# untitled.net
KiCad netlist of a schematic drawn in EAGLE
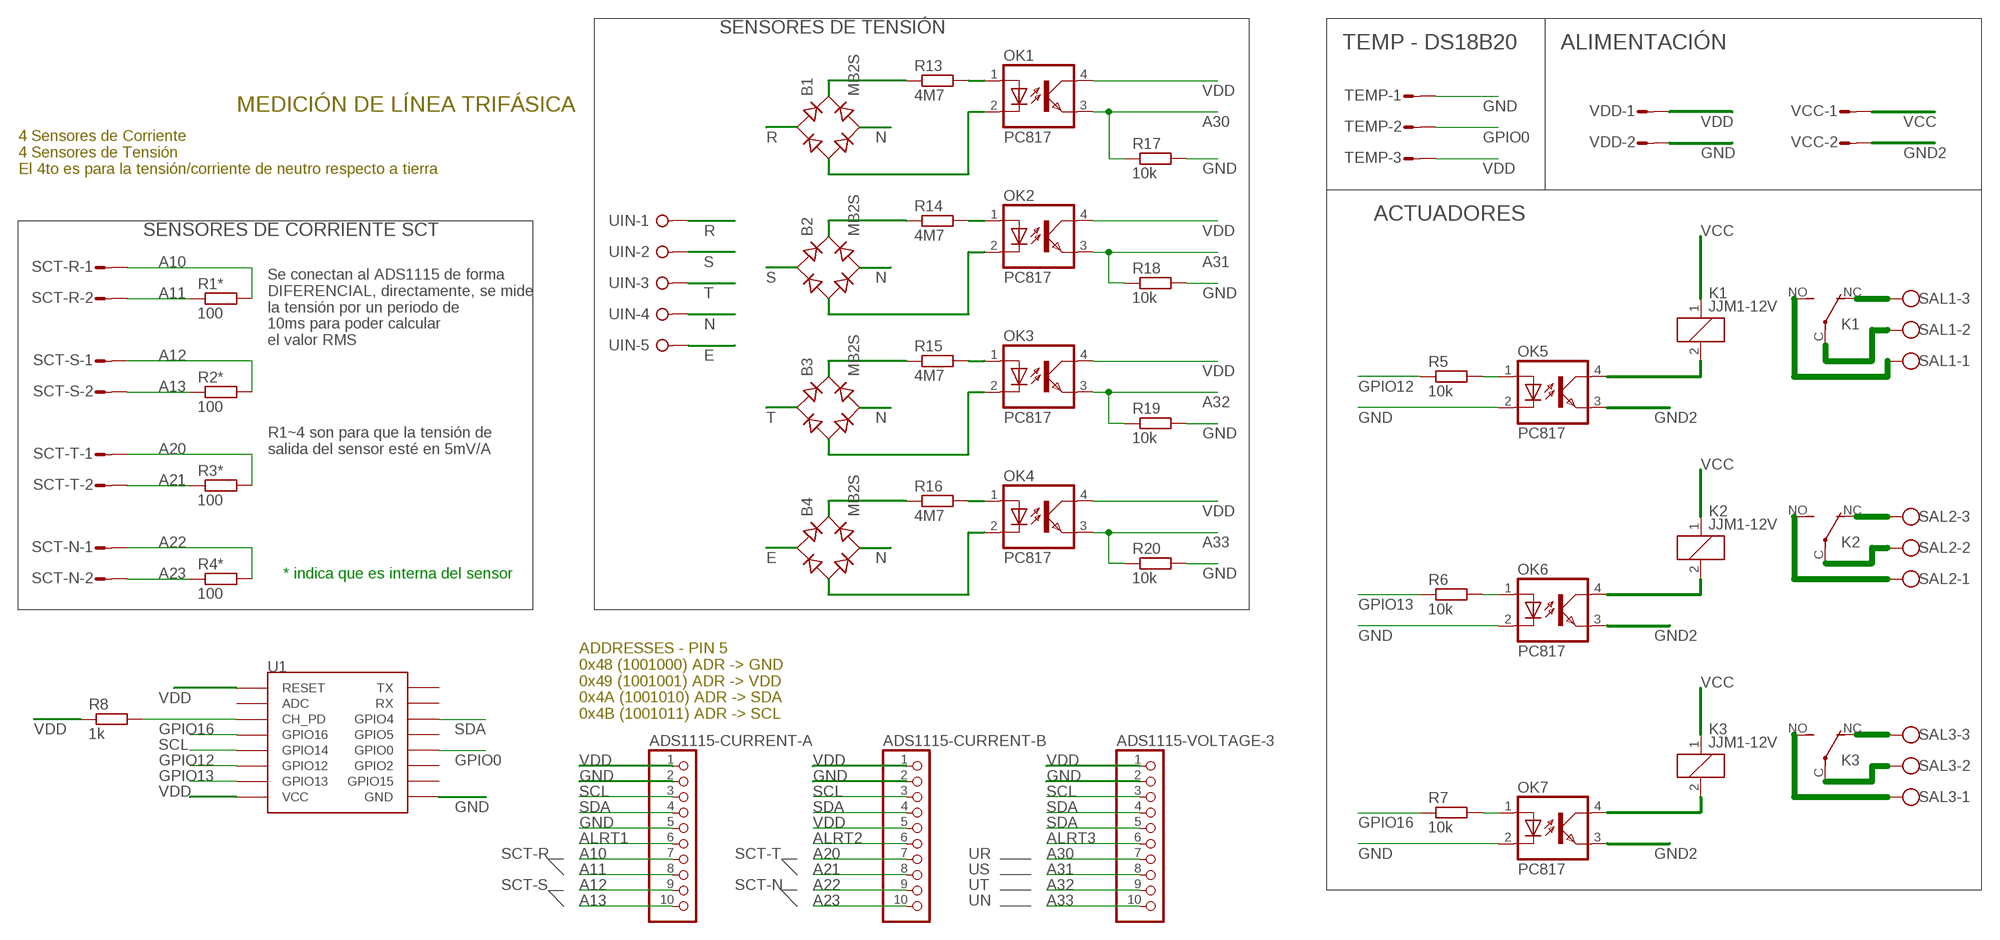
[diagram p0: schematic, sheet 1]

(export (version "E")
  (design (tool "Eeschema 10.0.6"))
  (components
    (comp (ref "ADS1115-CURRENT-A")
      (value "PINHD-1X10")
      (footprint "eagle-import:1X10")
      (libsource (lib "eagle-import") (part "PINHD-1X10"))
    )
    (comp (ref "ADS1115-CURRENT-B")
      (value "PINHD-1X10")
      (footprint "eagle-import:1X10")
      (libsource (lib "eagle-import") (part "PINHD-1X10"))
    )
    (comp (ref "ADS1115-VOLTAGE-3")
      (value "PINHD-1X10")
      (footprint "eagle-import:1X10")
      (libsource (lib "eagle-import") (part "PINHD-1X10"))
    )
    (comp (ref "B1")
      (value "MB2S")
      (footprint "eagle-import:SOIC-4")
      (libsource (lib "eagle-import") (part "MBS2"))
    )
    (comp (ref "B2")
      (value "MB2S")
      (footprint "eagle-import:SOIC-4")
      (libsource (lib "eagle-import") (part "MBS2"))
    )
    (comp (ref "B3")
      (value "MB2S")
      (footprint "eagle-import:SOIC-4")
      (libsource (lib "eagle-import") (part "MBS2"))
    )
    (comp (ref "B4")
      (value "MB2S")
      (footprint "eagle-import:SOIC-4")
      (libsource (lib "eagle-import") (part "MBS2"))
    )
    (comp (ref "K1")
      (value "JJM1-12V")
      (footprint "eagle-import:JJM1C")
      (fields (field (name "MF") "AROMAT/ MATSUSHITA"))
      (libsource (lib "eagle-import") (part "JJM1-12V"))
    )
    (comp (ref "K2")
      (value "JJM1-12V")
      (footprint "eagle-import:JJM1C")
      (fields (field (name "MF") "AROMAT/ MATSUSHITA"))
      (libsource (lib "eagle-import") (part "JJM1-12V"))
    )
    (comp (ref "K3")
      (value "JJM1-12V")
      (footprint "eagle-import:JJM1C")
      (fields (field (name "MF") "AROMAT/ MATSUSHITA"))
      (libsource (lib "eagle-import") (part "JJM1-12V"))
    )
    (comp (ref "OK1")
      (value "PC817")
      (footprint "eagle-import:DIL04")
      (fields (field (name "MPN") "PC817X4J000F"))
      (libsource (lib "eagle-import") (part "PC817"))
    )
    (comp (ref "OK2")
      (value "PC817")
      (footprint "eagle-import:DIL04")
      (fields (field (name "MPN") "PC817X4J000F"))
      (libsource (lib "eagle-import") (part "PC817"))
    )
    (comp (ref "OK3")
      (value "PC817")
      (footprint "eagle-import:DIL04")
      (fields (field (name "MPN") "PC817X4J000F"))
      (libsource (lib "eagle-import") (part "PC817"))
    )
    (comp (ref "OK4")
      (value "PC817")
      (footprint "eagle-import:DIL04")
      (fields (field (name "MPN") "PC817X4J000F"))
      (libsource (lib "eagle-import") (part "PC817"))
    )
    (comp (ref "OK5")
      (value "PC817")
      (footprint "eagle-import:DIL04")
      (fields (field (name "MPN") "PC817X4J000F"))
      (libsource (lib "eagle-import") (part "PC817"))
    )
    (comp (ref "OK6")
      (value "PC817")
      (footprint "eagle-import:DIL04")
      (fields (field (name "MPN") "PC817X4J000F"))
      (libsource (lib "eagle-import") (part "PC817"))
    )
    (comp (ref "OK7")
      (value "PC817")
      (footprint "eagle-import:DIL04")
      (fields (field (name "MPN") "PC817X4J000F"))
      (libsource (lib "eagle-import") (part "PC817"))
    )
    (comp (ref "R1*")
      (value "100")
      (footprint "eagle-import:M0805")
      (libsource (lib "eagle-import") (part "R-EU_M0805"))
    )
    (comp (ref "R2*")
      (value "100")
      (footprint "eagle-import:M0805")
      (libsource (lib "eagle-import") (part "R-EU_M0805"))
    )
    (comp (ref "R3*")
      (value "100")
      (footprint "eagle-import:M0805")
      (libsource (lib "eagle-import") (part "R-EU_M0805"))
    )
    (comp (ref "R4*")
      (value "100")
      (footprint "eagle-import:M0805")
      (libsource (lib "eagle-import") (part "R-EU_M0805"))
    )
    (comp (ref "R5")
      (value "10k")
      (footprint "eagle-import:M0805")
      (libsource (lib "eagle-import") (part "R-EU_M0805"))
    )
    (comp (ref "R6")
      (value "10k")
      (footprint "eagle-import:M0805")
      (libsource (lib "eagle-import") (part "R-EU_M0805"))
    )
    (comp (ref "R7")
      (value "10k")
      (footprint "eagle-import:M0805")
      (libsource (lib "eagle-import") (part "R-EU_M0805"))
    )
    (comp (ref "R8")
      (value "1k")
      (footprint "eagle-import:M0805")
      (libsource (lib "eagle-import") (part "R-EU_M0805"))
    )
    (comp (ref "R13")
      (value "4M7")
      (footprint "eagle-import:M0805")
      (libsource (lib "eagle-import") (part "R-EU_M0805"))
    )
    (comp (ref "R14")
      (value "4M7")
      (footprint "eagle-import:M0805")
      (libsource (lib "eagle-import") (part "R-EU_M0805"))
    )
    (comp (ref "R15")
      (value "4M7")
      (footprint "eagle-import:M0805")
      (libsource (lib "eagle-import") (part "R-EU_M0805"))
    )
    (comp (ref "R16")
      (value "4M7")
      (footprint "eagle-import:M0805")
      (libsource (lib "eagle-import") (part "R-EU_M0805"))
    )
    (comp (ref "R17")
      (value "10k")
      (footprint "eagle-import:M0805")
      (libsource (lib "eagle-import") (part "R-EU_M0805"))
    )
    (comp (ref "R18")
      (value "10k")
      (footprint "eagle-import:M0805")
      (libsource (lib "eagle-import") (part "R-EU_M0805"))
    )
    (comp (ref "R19")
      (value "10k")
      (footprint "eagle-import:M0805")
      (libsource (lib "eagle-import") (part "R-EU_M0805"))
    )
    (comp (ref "R20")
      (value "10k")
      (footprint "eagle-import:M0805")
      (libsource (lib "eagle-import") (part "R-EU_M0805"))
    )
    (comp (ref "SAL1")
      (value "W237-103")
      (footprint "eagle-import:W237-103")
      (fields (field (name "MPN") "237-103"))
      (libsource (lib "eagle-import") (part "W237-103"))
    )
    (comp (ref "SAL2")
      (value "W237-103")
      (footprint "eagle-import:W237-103")
      (fields (field (name "MPN") "237-103"))
      (libsource (lib "eagle-import") (part "W237-103"))
    )
    (comp (ref "SAL3")
      (value "W237-103")
      (footprint "eagle-import:W237-103")
      (fields (field (name "MPN") "237-103"))
      (libsource (lib "eagle-import") (part "W237-103"))
    )
    (comp (ref "SCT-N")
      (value "S02P")
      (footprint "eagle-import:S02P")
      (libsource (lib "eagle-import") (part "S02P"))
    )
    (comp (ref "SCT-R")
      (value "S02P")
      (footprint "eagle-import:S02P")
      (libsource (lib "eagle-import") (part "S02P"))
    )
    (comp (ref "SCT-S")
      (value "S02P")
      (footprint "eagle-import:S02P")
      (libsource (lib "eagle-import") (part "S02P"))
    )
    (comp (ref "SCT-T")
      (value "S02P")
      (footprint "eagle-import:S02P")
      (libsource (lib "eagle-import") (part "S02P"))
    )
    (comp (ref "TEMP")
      (value "S03P")
      (footprint "eagle-import:S03P")
      (libsource (lib "eagle-import") (part "S03P"))
    )
    (comp (ref "U1")
      (value "ESP12SMD")
      (footprint "eagle-import:ESP12-SMD")
      (libsource (lib "eagle-import") (part "ESP12SMD"))
    )
    (comp (ref "UIN")
      (value "W237-05P")
      (footprint "eagle-import:W237-5P")
      (libsource (lib "eagle-import") (part "W237-05P"))
    )
    (comp (ref "VCC")
      (value "S02P")
      (footprint "eagle-import:S02P")
      (libsource (lib "eagle-import") (part "S02P"))
    )
    (comp (ref "VDD")
      (value "S02P")
      (footprint "eagle-import:S02P")
      (libsource (lib "eagle-import") (part "S02P"))
    )
  )
  (nets
    (net (code "1") (name "/A10") (class "Default")
      (node (ref "ADS1115-CURRENT-A") (pin "7") (pinfunction "7_7") (pintype "passive"))
      (node (ref "R1*") (pin "2") (pinfunction "2_2") (pintype "passive"))
      (node (ref "SCT-R") (pin "1") (pinfunction "S_1") (pintype "passive"))
    )
    (net (code "2") (name "/A11") (class "Default")
      (node (ref "ADS1115-CURRENT-A") (pin "8") (pinfunction "8_8") (pintype "passive"))
      (node (ref "R1*") (pin "1") (pinfunction "1_1") (pintype "passive"))
      (node (ref "SCT-R") (pin "2") (pinfunction "S_2") (pintype "passive"))
    )
    (net (code "3") (name "/A12") (class "Default")
      (node (ref "ADS1115-CURRENT-A") (pin "9") (pinfunction "9_9") (pintype "passive"))
      (node (ref "R2*") (pin "2") (pinfunction "2_2") (pintype "passive"))
      (node (ref "SCT-S") (pin "1") (pinfunction "S_1") (pintype "passive"))
    )
    (net (code "4") (name "/A13") (class "Default")
      (node (ref "ADS1115-CURRENT-A") (pin "10") (pinfunction "10_10") (pintype "passive"))
      (node (ref "R2*") (pin "1") (pinfunction "1_1") (pintype "passive"))
      (node (ref "SCT-S") (pin "2") (pinfunction "S_2") (pintype "passive"))
    )
    (net (code "5") (name "/A20") (class "Default")
      (node (ref "ADS1115-CURRENT-B") (pin "7") (pinfunction "7_7") (pintype "passive"))
      (node (ref "R3*") (pin "2") (pinfunction "2_2") (pintype "passive"))
      (node (ref "SCT-T") (pin "1") (pinfunction "S_1") (pintype "passive"))
    )
    (net (code "6") (name "/A21") (class "Default")
      (node (ref "ADS1115-CURRENT-B") (pin "8") (pinfunction "8_8") (pintype "passive"))
      (node (ref "R3*") (pin "1") (pinfunction "1_1") (pintype "passive"))
      (node (ref "SCT-T") (pin "2") (pinfunction "S_2") (pintype "passive"))
    )
    (net (code "7") (name "/A22") (class "Default")
      (node (ref "ADS1115-CURRENT-B") (pin "9") (pinfunction "9_9") (pintype "passive"))
      (node (ref "R4*") (pin "2") (pinfunction "2_2") (pintype "passive"))
      (node (ref "SCT-N") (pin "1") (pinfunction "S_1") (pintype "passive"))
    )
    (net (code "8") (name "/A23") (class "Default")
      (node (ref "ADS1115-CURRENT-B") (pin "10") (pinfunction "10_10") (pintype "passive"))
      (node (ref "R4*") (pin "1") (pinfunction "1_1") (pintype "passive"))
      (node (ref "SCT-N") (pin "2") (pinfunction "S_2") (pintype "passive"))
    )
    (net (code "9") (name "/A30") (class "Default")
      (node (ref "ADS1115-VOLTAGE-3") (pin "7") (pinfunction "7_7") (pintype "passive"))
      (node (ref "OK1") (pin "3") (pinfunction "EMIT_3") (pintype "passive"))
      (node (ref "R17") (pin "1") (pinfunction "1_1") (pintype "passive"))
    )
    (net (code "10") (name "/A31") (class "Default")
      (node (ref "ADS1115-VOLTAGE-3") (pin "8") (pinfunction "8_8") (pintype "passive"))
      (node (ref "OK2") (pin "3") (pinfunction "EMIT_3") (pintype "passive"))
      (node (ref "R18") (pin "1") (pinfunction "1_1") (pintype "passive"))
    )
    (net (code "11") (name "/A32") (class "Default")
      (node (ref "ADS1115-VOLTAGE-3") (pin "9") (pinfunction "9_9") (pintype "passive"))
      (node (ref "OK3") (pin "3") (pinfunction "EMIT_3") (pintype "passive"))
      (node (ref "R19") (pin "1") (pinfunction "1_1") (pintype "passive"))
    )
    (net (code "12") (name "/A33") (class "Default")
      (node (ref "ADS1115-VOLTAGE-3") (pin "10") (pinfunction "10_10") (pintype "passive"))
      (node (ref "OK4") (pin "3") (pinfunction "EMIT_3") (pintype "passive"))
      (node (ref "R20") (pin "1") (pinfunction "1_1") (pintype "passive"))
    )
    (net (code "13") (name "/ALRT1") (class "Default")
      (node (ref "ADS1115-CURRENT-A") (pin "6") (pinfunction "6_6") (pintype "passive"))
    )
    (net (code "14") (name "/ALRT2") (class "Default")
      (node (ref "ADS1115-CURRENT-B") (pin "6") (pinfunction "6_6") (pintype "passive"))
    )
    (net (code "15") (name "/ALRT3") (class "Default")
      (node (ref "ADS1115-VOLTAGE-3") (pin "6") (pinfunction "6_6") (pintype "passive"))
    )
    (net (code "16") (name "/E") (class "Default")
      (node (ref "B4") (pin "~1") (pinfunction "AC1_~1") (pintype "passive"))
      (node (ref "UIN") (pin "5") (pinfunction "KL_5") (pintype "passive"))
    )
    (net (code "17") (name "/GND") (class "Default")
      (node (ref "ADS1115-CURRENT-A") (pin "2") (pinfunction "2_2") (pintype "passive"))
      (node (ref "ADS1115-CURRENT-A") (pin "5") (pinfunction "5_5") (pintype "passive"))
      (node (ref "ADS1115-CURRENT-B") (pin "2") (pinfunction "2_2") (pintype "passive"))
      (node (ref "ADS1115-VOLTAGE-3") (pin "2") (pinfunction "2_2") (pintype "passive"))
      (node (ref "OK5") (pin "2") (pinfunction "C_2") (pintype "passive"))
      (node (ref "OK6") (pin "2") (pinfunction "C_2") (pintype "passive"))
      (node (ref "OK7") (pin "2") (pinfunction "C_2") (pintype "passive"))
      (node (ref "R17") (pin "2") (pinfunction "2_2") (pintype "passive"))
      (node (ref "R18") (pin "2") (pinfunction "2_2") (pintype "passive"))
      (node (ref "R19") (pin "2") (pinfunction "2_2") (pintype "passive"))
      (node (ref "R20") (pin "2") (pinfunction "2_2") (pintype "passive"))
      (node (ref "TEMP") (pin "1") (pinfunction "S_1") (pintype "passive"))
      (node (ref "U1") (pin "GND") (pinfunction "GND_GND") (pintype "bidirectional"))
      (node (ref "VDD") (pin "2") (pinfunction "S_2") (pintype "passive"))
    )
    (net (code "18") (name "/GND2") (class "Default")
      (node (ref "OK5") (pin "3") (pinfunction "EMIT_3") (pintype "passive"))
      (node (ref "OK6") (pin "3") (pinfunction "EMIT_3") (pintype "passive"))
      (node (ref "OK7") (pin "3") (pinfunction "EMIT_3") (pintype "passive"))
      (node (ref "VCC") (pin "2") (pinfunction "S_2") (pintype "passive"))
    )
    (net (code "19") (name "/GPIO0") (class "Default")
      (node (ref "TEMP") (pin "2") (pinfunction "S_2") (pintype "passive"))
      (node (ref "U1") (pin "GPIO0") (pinfunction "GPIO0_GPIO0") (pintype "bidirectional"))
    )
    (net (code "20") (name "/GPIO12") (class "Default")
      (node (ref "R5") (pin "1") (pinfunction "1_1") (pintype "passive"))
      (node (ref "U1") (pin "GPIO12") (pinfunction "GPIO12_GPIO12") (pintype "bidirectional"))
    )
    (net (code "21") (name "/GPIO13") (class "Default")
      (node (ref "R6") (pin "1") (pinfunction "1_1") (pintype "passive"))
      (node (ref "U1") (pin "GPIO13") (pinfunction "GPIO13_GPIO13") (pintype "bidirectional"))
    )
    (net (code "22") (name "/GPIO16") (class "Default")
      (node (ref "R7") (pin "1") (pinfunction "1_1") (pintype "passive"))
      (node (ref "U1") (pin "GPIO16") (pinfunction "GPIO16_GPIO16") (pintype "bidirectional"))
    )
    (net (code "23") (name "/N") (class "Default")
      (node (ref "B1") (pin "~2") (pinfunction "AC2_~2") (pintype "passive"))
      (node (ref "B2") (pin "~2") (pinfunction "AC2_~2") (pintype "passive"))
      (node (ref "B3") (pin "~2") (pinfunction "AC2_~2") (pintype "passive"))
      (node (ref "B4") (pin "~2") (pinfunction "AC2_~2") (pintype "passive"))
      (node (ref "UIN") (pin "4") (pinfunction "KL_4") (pintype "passive"))
    )
    (net (code "24") (name "/R") (class "Default")
      (node (ref "B1") (pin "~1") (pinfunction "AC1_~1") (pintype "passive"))
      (node (ref "UIN") (pin "1") (pinfunction "KL_1") (pintype "passive"))
    )
    (net (code "25") (name "/S") (class "Default")
      (node (ref "B2") (pin "~1") (pinfunction "AC1_~1") (pintype "passive"))
      (node (ref "UIN") (pin "2") (pinfunction "KL_2") (pintype "passive"))
    )
    (net (code "26") (name "/SCL") (class "Default")
      (node (ref "ADS1115-CURRENT-A") (pin "3") (pinfunction "3_3") (pintype "passive"))
      (node (ref "ADS1115-CURRENT-B") (pin "3") (pinfunction "3_3") (pintype "passive"))
      (node (ref "ADS1115-VOLTAGE-3") (pin "3") (pinfunction "3_3") (pintype "passive"))
      (node (ref "U1") (pin "GPIO14") (pinfunction "GPIO14_GPIO14") (pintype "bidirectional"))
    )
    (net (code "27") (name "/SDA") (class "Default")
      (node (ref "ADS1115-CURRENT-A") (pin "4") (pinfunction "4_4") (pintype "passive"))
      (node (ref "ADS1115-CURRENT-B") (pin "4") (pinfunction "4_4") (pintype "passive"))
      (node (ref "ADS1115-VOLTAGE-3") (pin "4") (pinfunction "4_4") (pintype "passive"))
      (node (ref "ADS1115-VOLTAGE-3") (pin "5") (pinfunction "5_5") (pintype "passive"))
      (node (ref "U1") (pin "GPIO4") (pinfunction "GPIO4_GPIO4") (pintype "bidirectional"))
    )
    (net (code "28") (name "/T") (class "Default")
      (node (ref "B3") (pin "~1") (pinfunction "AC1_~1") (pintype "passive"))
      (node (ref "UIN") (pin "3") (pinfunction "KL_3") (pintype "passive"))
    )
    (net (code "29") (name "/VCC") (class "Default")
      (node (ref "K1") (pin "1") (pinfunction "1_1") (pintype "passive"))
      (node (ref "K2") (pin "1") (pinfunction "1_1") (pintype "passive"))
      (node (ref "K3") (pin "1") (pinfunction "1_1") (pintype "passive"))
      (node (ref "VCC") (pin "1") (pinfunction "S_1") (pintype "passive"))
    )
    (net (code "30") (name "/VDD") (class "Default")
      (node (ref "ADS1115-CURRENT-A") (pin "1") (pinfunction "1_1") (pintype "passive"))
      (node (ref "ADS1115-CURRENT-B") (pin "1") (pinfunction "1_1") (pintype "passive"))
      (node (ref "ADS1115-CURRENT-B") (pin "5") (pinfunction "5_5") (pintype "passive"))
      (node (ref "ADS1115-VOLTAGE-3") (pin "1") (pinfunction "1_1") (pintype "passive"))
      (node (ref "OK1") (pin "4") (pinfunction "COL_4") (pintype "passive"))
      (node (ref "OK2") (pin "4") (pinfunction "COL_4") (pintype "passive"))
      (node (ref "OK3") (pin "4") (pinfunction "COL_4") (pintype "passive"))
      (node (ref "OK4") (pin "4") (pinfunction "COL_4") (pintype "passive"))
      (node (ref "R8") (pin "1") (pinfunction "1_1") (pintype "passive"))
      (node (ref "TEMP") (pin "3") (pinfunction "S_3") (pintype "passive"))
      (node (ref "U1") (pin "RESET") (pinfunction "RESET_RESET") (pintype "bidirectional"))
      (node (ref "U1") (pin "VCC") (pinfunction "VCC_VCC") (pintype "bidirectional"))
      (node (ref "VDD") (pin "1") (pinfunction "S_1") (pintype "passive"))
    )
    (net (code "31") (name "Net-(B1-Pad+)") (class "Default")
      (node (ref "B1") (pin "+") (pinfunction "+_+") (pintype "passive"))
      (node (ref "R13") (pin "1") (pinfunction "1_1") (pintype "passive"))
    )
    (net (code "32") (name "Net-(B2-Pad+)") (class "Default")
      (node (ref "B2") (pin "+") (pinfunction "+_+") (pintype "passive"))
      (node (ref "R14") (pin "1") (pinfunction "1_1") (pintype "passive"))
    )
    (net (code "33") (name "Net-(B3-Pad+)") (class "Default")
      (node (ref "B3") (pin "+") (pinfunction "+_+") (pintype "passive"))
      (node (ref "R15") (pin "1") (pinfunction "1_1") (pintype "passive"))
    )
    (net (code "34") (name "Net-(B4-Pad+)") (class "Default")
      (node (ref "B4") (pin "+") (pinfunction "+_+") (pintype "passive"))
      (node (ref "R16") (pin "1") (pinfunction "1_1") (pintype "passive"))
    )
    (net (code "35") (name "Net-(K1B-O)") (class "Default")
      (node (ref "K1") (pin "NC") (pinfunction "O_NC") (pintype "passive"))
      (node (ref "SAL1") (pin "3") (pinfunction "KL_3") (pintype "passive"))
    )
    (net (code "36") (name "Net-(K1B-P)") (class "Default")
      (node (ref "K1") (pin "C") (pinfunction "P_C") (pintype "passive"))
      (node (ref "SAL1") (pin "2") (pinfunction "KL_2") (pintype "passive"))
    )
    (net (code "37") (name "Net-(K1B-S)") (class "Default")
      (node (ref "K1") (pin "NO") (pinfunction "S_NO") (pintype "passive"))
      (node (ref "SAL1") (pin "1") (pinfunction "KL_1") (pintype "passive"))
    )
    (net (code "38") (name "Net-(K2B-O)") (class "Default")
      (node (ref "K2") (pin "NC") (pinfunction "O_NC") (pintype "passive"))
      (node (ref "SAL2") (pin "3") (pinfunction "KL_3") (pintype "passive"))
    )
    (net (code "39") (name "Net-(K2B-P)") (class "Default")
      (node (ref "K2") (pin "C") (pinfunction "P_C") (pintype "passive"))
      (node (ref "SAL2") (pin "2") (pinfunction "KL_2") (pintype "passive"))
    )
    (net (code "40") (name "Net-(K2B-S)") (class "Default")
      (node (ref "K2") (pin "NO") (pinfunction "S_NO") (pintype "passive"))
      (node (ref "SAL2") (pin "1") (pinfunction "KL_1") (pintype "passive"))
    )
    (net (code "41") (name "Net-(K3B-O)") (class "Default")
      (node (ref "K3") (pin "NC") (pinfunction "O_NC") (pintype "passive"))
      (node (ref "SAL3") (pin "3") (pinfunction "KL_3") (pintype "passive"))
    )
    (net (code "42") (name "Net-(K3B-P)") (class "Default")
      (node (ref "K3") (pin "C") (pinfunction "P_C") (pintype "passive"))
      (node (ref "SAL3") (pin "2") (pinfunction "KL_2") (pintype "passive"))
    )
    (net (code "43") (name "Net-(K3B-S)") (class "Default")
      (node (ref "K3") (pin "NO") (pinfunction "S_NO") (pintype "passive"))
      (node (ref "SAL3") (pin "1") (pinfunction "KL_1") (pintype "passive"))
    )
    (net (code "44") (name "Net-(OK1-A)") (class "Default")
      (node (ref "OK1") (pin "1") (pinfunction "A_1") (pintype "passive"))
      (node (ref "R13") (pin "2") (pinfunction "2_2") (pintype "passive"))
    )
    (net (code "45") (name "Net-(OK1-C)") (class "Default")
      (node (ref "B1") (pin "-") (pinfunction "-_-") (pintype "passive"))
      (node (ref "OK1") (pin "2") (pinfunction "C_2") (pintype "passive"))
    )
    (net (code "46") (name "Net-(OK2-A)") (class "Default")
      (node (ref "OK2") (pin "1") (pinfunction "A_1") (pintype "passive"))
      (node (ref "R14") (pin "2") (pinfunction "2_2") (pintype "passive"))
    )
    (net (code "47") (name "Net-(OK2-C)") (class "Default")
      (node (ref "B2") (pin "-") (pinfunction "-_-") (pintype "passive"))
      (node (ref "OK2") (pin "2") (pinfunction "C_2") (pintype "passive"))
    )
    (net (code "48") (name "Net-(OK3-A)") (class "Default")
      (node (ref "OK3") (pin "1") (pinfunction "A_1") (pintype "passive"))
      (node (ref "R15") (pin "2") (pinfunction "2_2") (pintype "passive"))
    )
    (net (code "49") (name "Net-(OK3-C)") (class "Default")
      (node (ref "B3") (pin "-") (pinfunction "-_-") (pintype "passive"))
      (node (ref "OK3") (pin "2") (pinfunction "C_2") (pintype "passive"))
    )
    (net (code "50") (name "Net-(OK4-A)") (class "Default")
      (node (ref "OK4") (pin "1") (pinfunction "A_1") (pintype "passive"))
      (node (ref "R16") (pin "2") (pinfunction "2_2") (pintype "passive"))
    )
    (net (code "51") (name "Net-(OK4-C)") (class "Default")
      (node (ref "B4") (pin "-") (pinfunction "-_-") (pintype "passive"))
      (node (ref "OK4") (pin "2") (pinfunction "C_2") (pintype "passive"))
    )
    (net (code "52") (name "Net-(OK5-A)") (class "Default")
      (node (ref "OK5") (pin "1") (pinfunction "A_1") (pintype "passive"))
      (node (ref "R5") (pin "2") (pinfunction "2_2") (pintype "passive"))
    )
    (net (code "53") (name "Net-(OK5-COL)") (class "Default")
      (node (ref "K1") (pin "2") (pinfunction "2_2") (pintype "passive"))
      (node (ref "OK5") (pin "4") (pinfunction "COL_4") (pintype "passive"))
    )
    (net (code "54") (name "Net-(OK6-A)") (class "Default")
      (node (ref "OK6") (pin "1") (pinfunction "A_1") (pintype "passive"))
      (node (ref "R6") (pin "2") (pinfunction "2_2") (pintype "passive"))
    )
    (net (code "55") (name "Net-(OK6-COL)") (class "Default")
      (node (ref "K2") (pin "2") (pinfunction "2_2") (pintype "passive"))
      (node (ref "OK6") (pin "4") (pinfunction "COL_4") (pintype "passive"))
    )
    (net (code "56") (name "Net-(OK7-A)") (class "Default")
      (node (ref "OK7") (pin "1") (pinfunction "A_1") (pintype "passive"))
      (node (ref "R7") (pin "2") (pinfunction "2_2") (pintype "passive"))
    )
    (net (code "57") (name "Net-(OK7-COL)") (class "Default")
      (node (ref "K3") (pin "2") (pinfunction "2_2") (pintype "passive"))
      (node (ref "OK7") (pin "4") (pinfunction "COL_4") (pintype "passive"))
    )
    (net (code "58") (name "Net-(R8-Pad2)") (class "Default")
      (node (ref "R8") (pin "2") (pinfunction "2_2") (pintype "passive"))
      (node (ref "U1") (pin "CH_PD") (pinfunction "CH_PD_CH_PD") (pintype "bidirectional"))
    )
    (net (code "59") (name "unconnected-(U1-PadADC)") (class "Default")
      (node (ref "U1") (pin "ADC") (pinfunction "ADC_ADC") (pintype "bidirectional"))
    )
    (net (code "60") (name "unconnected-(U1-PadGPIO2)") (class "Default")
      (node (ref "U1") (pin "GPIO2") (pinfunction "GPIO2_GPIO2") (pintype "bidirectional"))
    )
    (net (code "61") (name "unconnected-(U1-PadGPIO5)") (class "Default")
      (node (ref "U1") (pin "GPIO5") (pinfunction "GPIO5_GPIO5") (pintype "bidirectional"))
    )
    (net (code "62") (name "unconnected-(U1-PadGPIO15)") (class "Default")
      (node (ref "U1") (pin "GPIO15") (pinfunction "GPIO15_GPIO15") (pintype "bidirectional"))
    )
    (net (code "63") (name "unconnected-(U1-RX-PadRXD0)") (class "Default")
      (node (ref "U1") (pin "RXD0") (pinfunction "RX_RXD0") (pintype "bidirectional"))
    )
    (net (code "64") (name "unconnected-(U1-TX-PadTXD0)") (class "Default")
      (node (ref "U1") (pin "TXD0") (pinfunction "TX_TXD0") (pintype "bidirectional"))
    )
  )
)
